# 40khz_ultrasonic_transmitter.net
KiCad netlist of a schematic drawn in EAGLE
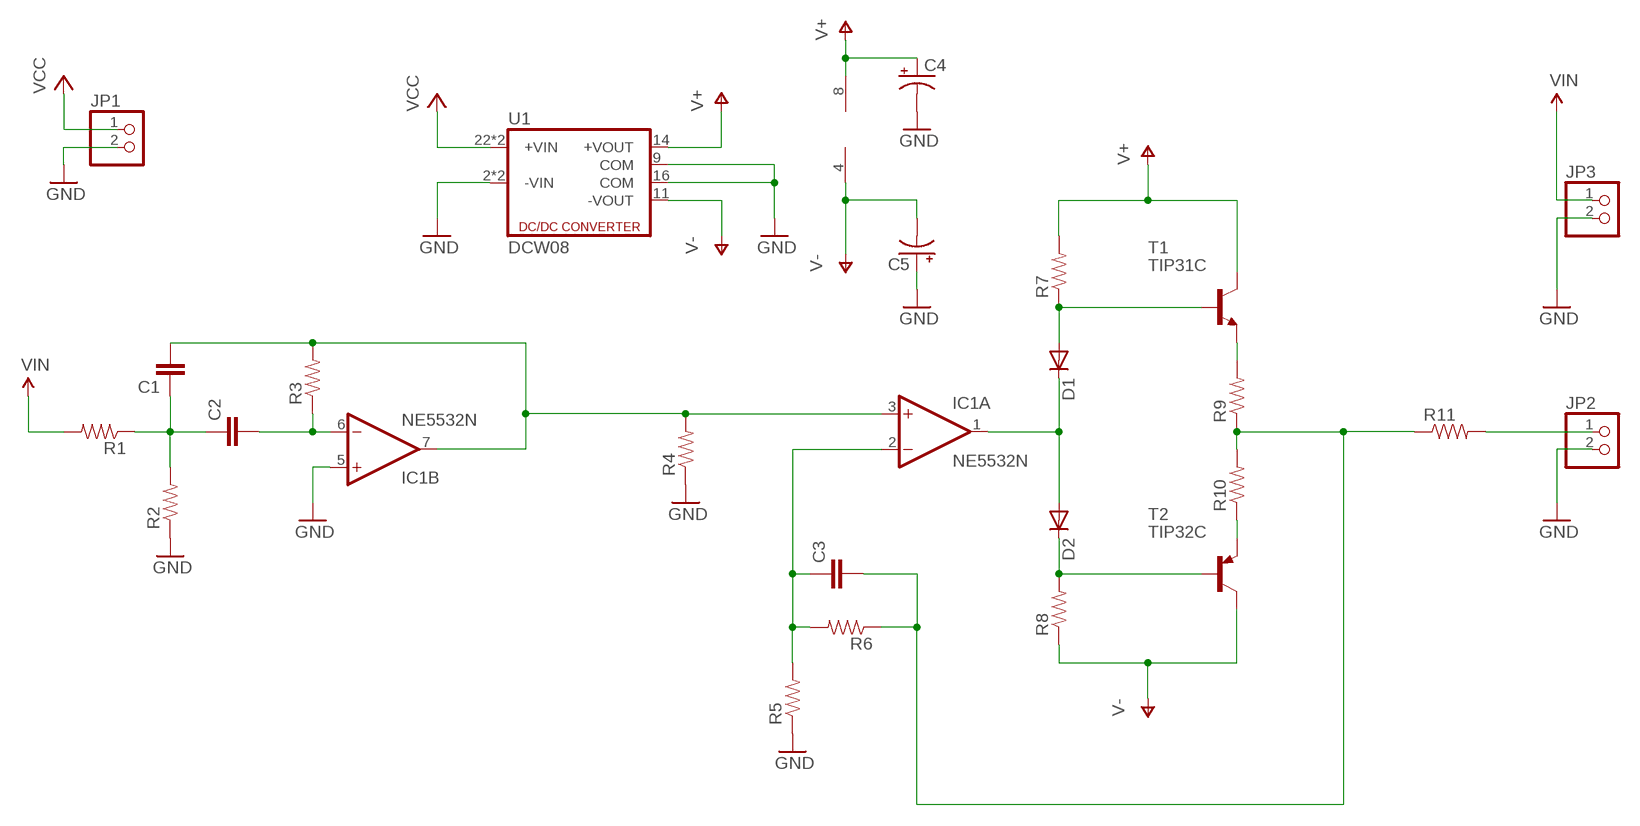
[diagram p0: schematic, sheet 1]

(export (version "E")
  (design (tool "Eeschema 10.0.6"))
  (components
    (comp (ref "C1")
      (value "CAPPTH2")
      (footprint "eagle-import:CAP-PTH-SMALL2")
      (libsource (lib "eagle-import") (part "CAPPTH2"))
    )
    (comp (ref "C2")
      (value "CAPPTH2")
      (footprint "eagle-import:CAP-PTH-SMALL2")
      (libsource (lib "eagle-import") (part "CAPPTH2"))
    )
    (comp (ref "C3")
      (value "CAPPTH2")
      (footprint "eagle-import:CAP-PTH-SMALL2")
      (libsource (lib "eagle-import") (part "CAPPTH2"))
    )
    (comp (ref "C4")
      (value "CAP_POLPTH1")
      (footprint "eagle-import:CPOL-RADIAL-100UF-25V")
      (libsource (lib "eagle-import") (part "CAP_POLPTH1"))
    )
    (comp (ref "C5")
      (value "CAP_POLPTH1")
      (footprint "eagle-import:CPOL-RADIAL-100UF-25V")
      (libsource (lib "eagle-import") (part "CAP_POLPTH1"))
    )
    (comp (ref "D1")
      (value "DIODE1N4148")
      (footprint "eagle-import:DIODE-1N4148")
      (libsource (lib "eagle-import") (part "DIODE1N4148"))
    )
    (comp (ref "D2")
      (value "DIODE1N4148")
      (footprint "eagle-import:DIODE-1N4148")
      (libsource (lib "eagle-import") (part "DIODE1N4148"))
    )
    (comp (ref "IC1")
      (value "NE5532N")
      (footprint "eagle-import:DIL08")
      (libsource (lib "eagle-import") (part "NE5532N"))
    )
    (comp (ref "JP1")
      (value "PINHD-1X2")
      (footprint "eagle-import:1X02")
      (libsource (lib "eagle-import") (part "PINHD-1X2"))
    )
    (comp (ref "JP2")
      (value "PINHD-1X2")
      (footprint "eagle-import:1X02")
      (libsource (lib "eagle-import") (part "PINHD-1X2"))
    )
    (comp (ref "JP3")
      (value "PINHD-1X2")
      (footprint "eagle-import:1X02")
      (libsource (lib "eagle-import") (part "PINHD-1X2"))
    )
    (comp (ref "R1")
      (value "RESISTORPTH-1/4W")
      (footprint "eagle-import:AXIAL-0.4")
      (libsource (lib "eagle-import") (part "RESISTORPTH-1/4W"))
    )
    (comp (ref "R2")
      (value "RESISTORPTH-1/4W")
      (footprint "eagle-import:AXIAL-0.4")
      (libsource (lib "eagle-import") (part "RESISTORPTH-1/4W"))
    )
    (comp (ref "R3")
      (value "RESISTORPTH-1/4W")
      (footprint "eagle-import:AXIAL-0.4")
      (libsource (lib "eagle-import") (part "RESISTORPTH-1/4W"))
    )
    (comp (ref "R4")
      (value "RESISTORPTH-1/4W")
      (footprint "eagle-import:AXIAL-0.4")
      (libsource (lib "eagle-import") (part "RESISTORPTH-1/4W"))
    )
    (comp (ref "R5")
      (value "RESISTORPTH-1/4W")
      (footprint "eagle-import:AXIAL-0.4")
      (libsource (lib "eagle-import") (part "RESISTORPTH-1/4W"))
    )
    (comp (ref "R6")
      (value "RESISTORPTH-1/4W")
      (footprint "eagle-import:AXIAL-0.4")
      (libsource (lib "eagle-import") (part "RESISTORPTH-1/4W"))
    )
    (comp (ref "R7")
      (value "RESISTORPTH-1/4W")
      (footprint "eagle-import:AXIAL-0.4")
      (libsource (lib "eagle-import") (part "RESISTORPTH-1/4W"))
    )
    (comp (ref "R8")
      (value "RESISTORPTH-1/4W")
      (footprint "eagle-import:AXIAL-0.4")
      (libsource (lib "eagle-import") (part "RESISTORPTH-1/4W"))
    )
    (comp (ref "R9")
      (value "RESISTORPTH-1/4W")
      (footprint "eagle-import:AXIAL-0.4")
      (libsource (lib "eagle-import") (part "RESISTORPTH-1/4W"))
    )
    (comp (ref "R10")
      (value "RESISTORPTH-1/4W")
      (footprint "eagle-import:AXIAL-0.4")
      (libsource (lib "eagle-import") (part "RESISTORPTH-1/4W"))
    )
    (comp (ref "R11")
      (value "RESISTORPTH-2W")
      (footprint "eagle-import:AXIAL-0.8")
      (libsource (lib "eagle-import") (part "RESISTORPTH-2W"))
    )
    (comp (ref "T1")
      (value "TIP31C")
      (footprint "eagle-import:TO220")
      (libsource (lib "eagle-import") (part "TIP31C"))
    )
    (comp (ref "T2")
      (value "TIP32C")
      (footprint "eagle-import:TO220")
      (libsource (lib "eagle-import") (part "TIP32C"))
    )
    (comp (ref "U1")
      (value "DCW08")
      (footprint "eagle-import:DCW08")
      (libsource (lib "eagle-import") (part "DCW08"))
    )
  )
  (nets
    (net (code "1") (name "GND") (class "Default")
      (node (ref "C4") (pin "2") (pinfunction "-_2") (pintype "passive"))
      (node (ref "C5") (pin "1") (pinfunction "+_1") (pintype "passive"))
      (node (ref "IC1") (pin "5") (pinfunction "+IN_5") (pintype "input"))
      (node (ref "JP1") (pin "2") (pinfunction "2_2") (pintype "passive"))
      (node (ref "JP2") (pin "2") (pinfunction "2_2") (pintype "passive"))
      (node (ref "JP3") (pin "2") (pinfunction "2_2") (pintype "passive"))
      (node (ref "R2") (pin "P$1") (pinfunction "1_P$1") (pintype "passive"))
      (node (ref "R4") (pin "P$1") (pinfunction "1_P$1") (pintype "passive"))
      (node (ref "R5") (pin "P$1") (pinfunction "1_P$1") (pintype "passive"))
      (node (ref "U1") (pin "16") (pinfunction "COM_16") (pintype "passive"))
      (node (ref "U1") (pin "2") (pinfunction "-VIN_2") (pintype "passive"))
      (node (ref "U1") (pin "3") (pinfunction "-VIN_3") (pintype "passive"))
      (node (ref "U1") (pin "9") (pinfunction "COM_9") (pintype "passive"))
    )
    (net (code "2") (name "Net-(IC1A-+IN)") (class "Default")
      (node (ref "C1") (pin "2") (pinfunction "2_2") (pintype "passive"))
      (node (ref "IC1") (pin "3") (pinfunction "+IN_3") (pintype "input"))
      (node (ref "IC1") (pin "7") (pinfunction "OUT_7") (pintype "output"))
      (node (ref "R3") (pin "P$2") (pinfunction "2_P$2") (pintype "passive"))
      (node (ref "R4") (pin "P$2") (pinfunction "2_P$2") (pintype "passive"))
    )
    (net (code "3") (name "Net-(IC1A--IN)") (class "Default")
      (node (ref "C3") (pin "1") (pinfunction "1_1") (pintype "passive"))
      (node (ref "IC1") (pin "2") (pinfunction "-IN_2") (pintype "input"))
      (node (ref "R5") (pin "P$2") (pinfunction "2_P$2") (pintype "passive"))
      (node (ref "R6") (pin "P$2") (pinfunction "2_P$2") (pintype "passive"))
    )
    (net (code "4") (name "Net-(IC1A-OUT)") (class "Default")
      (node (ref "D1") (pin "C") (pinfunction "C_C") (pintype "passive"))
      (node (ref "D2") (pin "A") (pinfunction "A_A") (pintype "passive"))
      (node (ref "IC1") (pin "1") (pinfunction "OUT_1") (pintype "output"))
    )
    (net (code "5") (name "Net-(IC1B--IN)") (class "Default")
      (node (ref "C2") (pin "2") (pinfunction "2_2") (pintype "passive"))
      (node (ref "IC1") (pin "6") (pinfunction "-IN_6") (pintype "input"))
      (node (ref "R3") (pin "P$1") (pinfunction "1_P$1") (pintype "passive"))
    )
    (net (code "6") (name "Net-(R1-1)") (class "Default")
      (node (ref "C1") (pin "1") (pinfunction "1_1") (pintype "passive"))
      (node (ref "C2") (pin "1") (pinfunction "1_1") (pintype "passive"))
      (node (ref "R1") (pin "P$1") (pinfunction "1_P$1") (pintype "passive"))
      (node (ref "R2") (pin "P$2") (pinfunction "2_P$2") (pintype "passive"))
    )
    (net (code "7") (name "Net-(R7-1)") (class "Default")
      (node (ref "D1") (pin "A") (pinfunction "A_A") (pintype "passive"))
      (node (ref "R7") (pin "P$1") (pinfunction "1_P$1") (pintype "passive"))
      (node (ref "T1") (pin "1") (pinfunction "B_1") (pintype "passive"))
    )
    (net (code "8") (name "Net-(R8-2)") (class "Default")
      (node (ref "D2") (pin "C") (pinfunction "C_C") (pintype "passive"))
      (node (ref "R8") (pin "P$2") (pinfunction "2_P$2") (pintype "passive"))
      (node (ref "T2") (pin "1") (pinfunction "B_1") (pintype "passive"))
    )
    (net (code "9") (name "Net-(R9-2)") (class "Default")
      (node (ref "R9") (pin "P$2") (pinfunction "2_P$2") (pintype "passive"))
      (node (ref "T1") (pin "3") (pinfunction "E_3") (pintype "passive"))
    )
    (net (code "10") (name "Net-(R10-1)") (class "Default")
      (node (ref "R10") (pin "P$1") (pinfunction "1_P$1") (pintype "passive"))
      (node (ref "T2") (pin "3") (pinfunction "E_3") (pintype "passive"))
    )
    (net (code "11") (name "Net-(R10-2)") (class "Default")
      (node (ref "C3") (pin "2") (pinfunction "2_2") (pintype "passive"))
      (node (ref "R10") (pin "P$2") (pinfunction "2_P$2") (pintype "passive"))
      (node (ref "R11") (pin "P$1") (pinfunction "1_P$1") (pintype "passive"))
      (node (ref "R6") (pin "P$1") (pinfunction "1_P$1") (pintype "passive"))
      (node (ref "R9") (pin "P$1") (pinfunction "1_P$1") (pintype "passive"))
    )
    (net (code "12") (name "Net-(R11-2)") (class "Default")
      (node (ref "JP2") (pin "1") (pinfunction "1_1") (pintype "passive"))
      (node (ref "R11") (pin "P$2") (pinfunction "2_P$2") (pintype "passive"))
    )
    (net (code "13") (name "V+") (class "Default")
      (node (ref "C4") (pin "1") (pinfunction "+_1") (pintype "passive"))
      (node (ref "IC1") (pin "8") (pinfunction "V+_8") (pintype "power_in"))
      (node (ref "R7") (pin "P$2") (pinfunction "2_P$2") (pintype "passive"))
      (node (ref "T1") (pin "2") (pinfunction "C_2") (pintype "passive"))
      (node (ref "U1") (pin "14") (pinfunction "+VOUT_14") (pintype "passive"))
    )
    (net (code "14") (name "V-") (class "Default")
      (node (ref "C5") (pin "2") (pinfunction "-_2") (pintype "passive"))
      (node (ref "IC1") (pin "4") (pinfunction "V-_4") (pintype "power_in"))
      (node (ref "R8") (pin "P$1") (pinfunction "1_P$1") (pintype "passive"))
      (node (ref "T2") (pin "2") (pinfunction "C_2") (pintype "passive"))
      (node (ref "U1") (pin "11") (pinfunction "-VOUT_11") (pintype "passive"))
    )
    (net (code "15") (name "VCC") (class "Default")
      (node (ref "JP1") (pin "1") (pinfunction "1_1") (pintype "passive"))
      (node (ref "U1") (pin "22") (pinfunction "+VIN_22") (pintype "passive"))
      (node (ref "U1") (pin "23") (pinfunction "+VIN_23") (pintype "passive"))
    )
    (net (code "16") (name "VIN") (class "Default")
      (node (ref "JP3") (pin "1") (pinfunction "1_1") (pintype "passive"))
      (node (ref "R1") (pin "P$2") (pinfunction "2_P$2") (pintype "passive"))
    )
  )
)
